# receiver.net
KiCad netlist of a schematic drawn in EAGLE
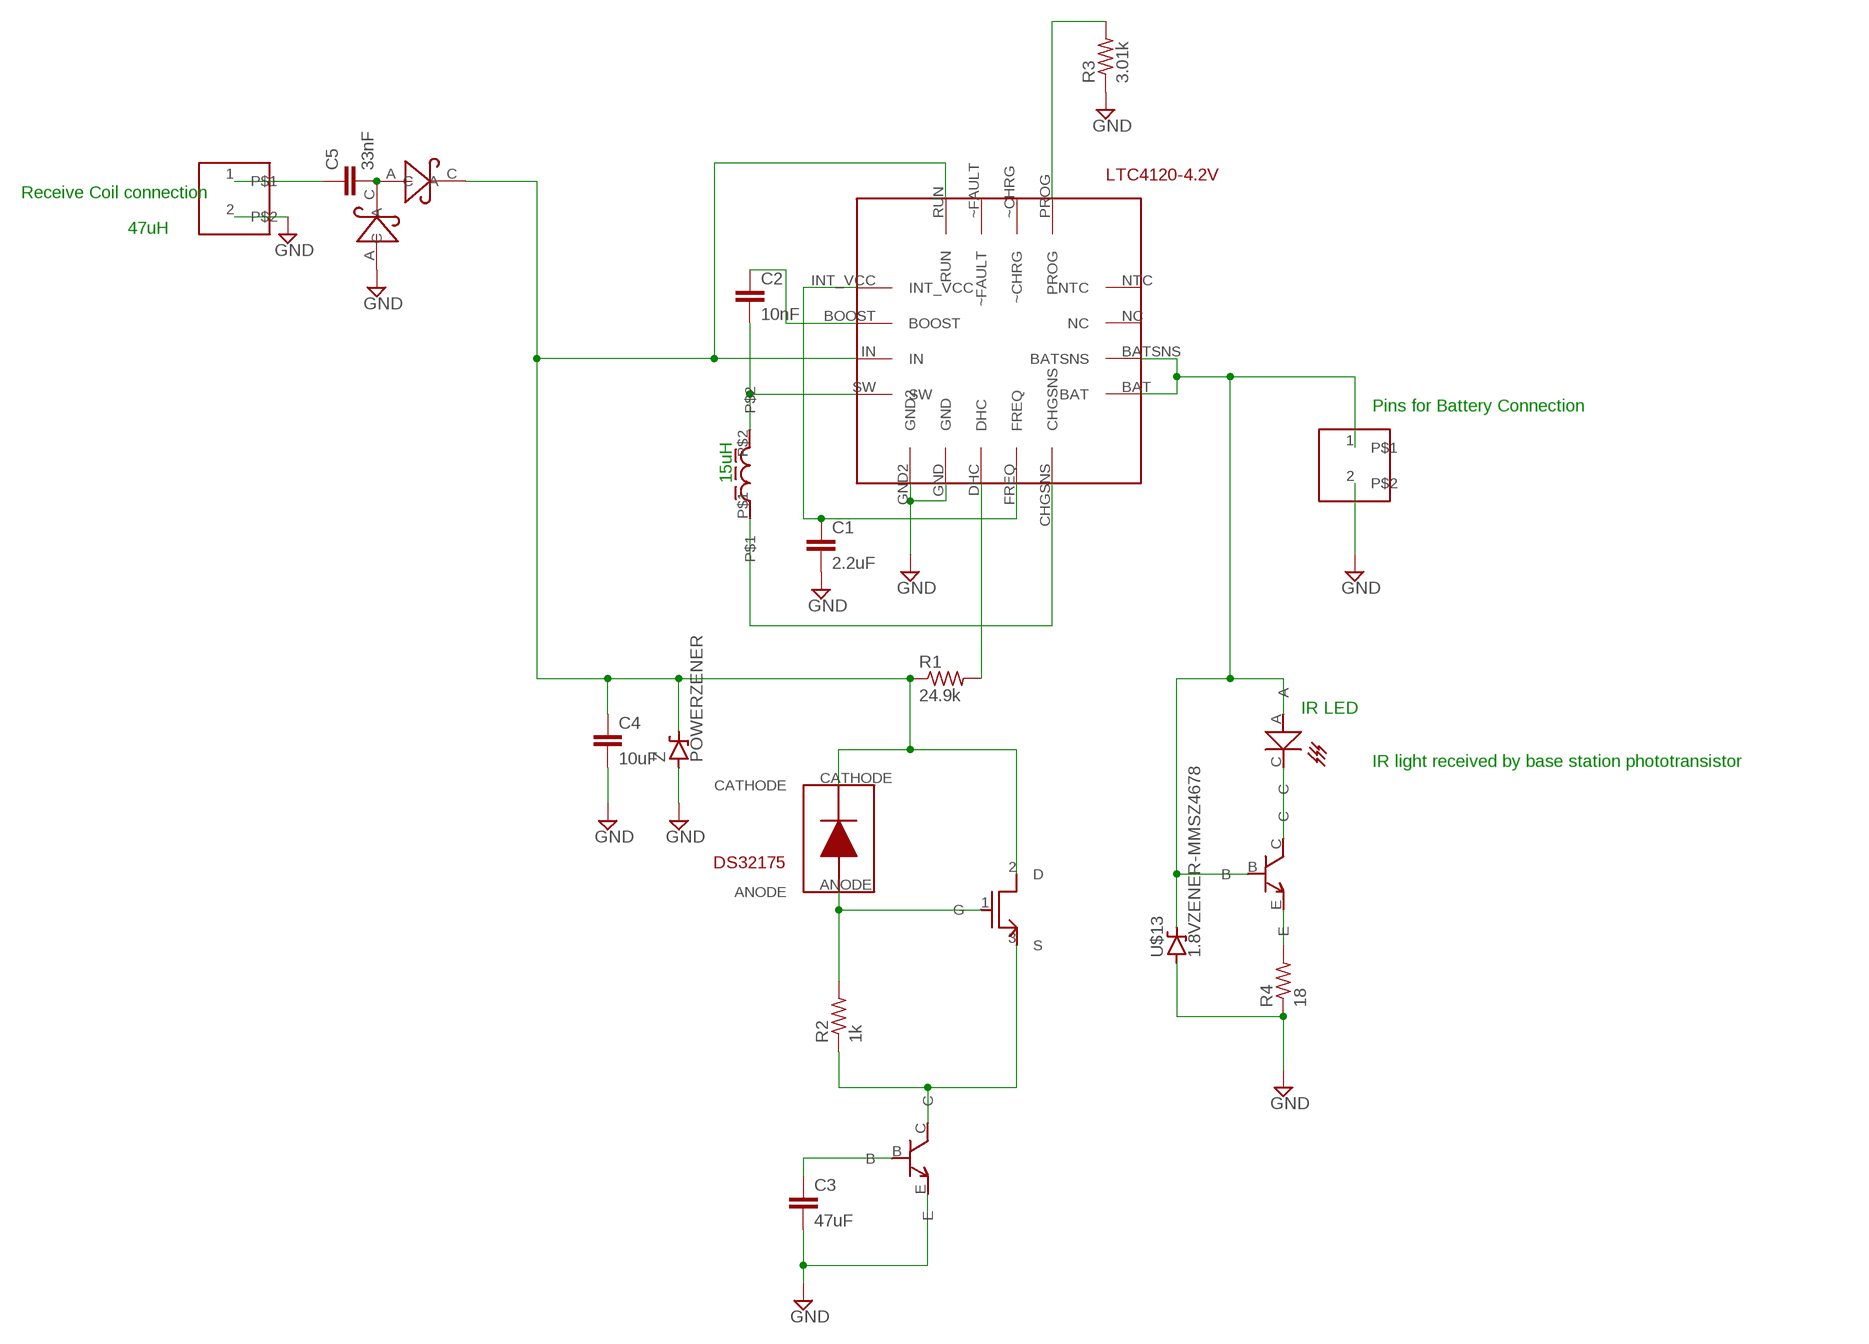
[diagram p0: schematic, sheet 1]

(export (version "E")
  (design (tool "Eeschema 10.0.6"))
  (components
    (comp (ref "C1")
      (value "2.2uF")
      (footprint "eagle-import:C0805K")
      (libsource (lib "eagle-import") (part "C-EUC0805K"))
    )
    (comp (ref "C2")
      (value "10nF")
      (footprint "eagle-import:C0805K")
      (libsource (lib "eagle-import") (part "C-EUC0805K"))
    )
    (comp (ref "C3")
      (value "47uF")
      (footprint "eagle-import:C0805K")
      (libsource (lib "eagle-import") (part "C-EUC0805K"))
    )
    (comp (ref "C4")
      (value "10uF")
      (footprint "eagle-import:C0805K")
      (libsource (lib "eagle-import") (part "C-EUC0805K"))
    )
    (comp (ref "C5")
      (value "33nF")
      (footprint "eagle-import:C0805K")
      (libsource (lib "eagle-import") (part "C-EUC0805K"))
    )
    (comp (ref "PS")
      (value "SCHTKYPOWER")
      (footprint "eagle-import:POWERDI123")
      (libsource (lib "eagle-import") (part "SCHTKYPOWER"))
    )
    (comp (ref "PS2")
      (value "SCHTKYPOWER")
      (footprint "eagle-import:POWERDI123")
      (libsource (lib "eagle-import") (part "SCHTKYPOWER"))
    )
    (comp (ref "R1")
      (value "24.9k")
      (footprint "eagle-import:R0805")
      (libsource (lib "eagle-import") (part "R-US_R0805"))
    )
    (comp (ref "R2")
      (value "1k")
      (footprint "eagle-import:R0805")
      (libsource (lib "eagle-import") (part "R-US_R0805"))
    )
    (comp (ref "R3")
      (value "3.01k")
      (footprint "eagle-import:R0805")
      (libsource (lib "eagle-import") (part "R-US_R0805"))
    )
    (comp (ref "R4")
      (value "18")
      (footprint "eagle-import:R0805")
      (libsource (lib "eagle-import") (part "R-US_R0805"))
    )
    (comp (ref "U$1")
      (value "LTC4120-4.2V")
      (footprint "eagle-import:LTC4120-4.2V")
      (libsource (lib "eagle-import") (part "LTC4120-4.2V"))
    )
    (comp (ref "U$2")
      (value "1X02")
      (footprint "eagle-import:1X02")
      (libsource (lib "eagle-import") (part "1X02"))
    )
    (comp (ref "U$3")
      (value "15UH-INDUCTOR")
      (footprint "eagle-import:15UH-INDUCTOR")
      (libsource (lib "eagle-import") (part "15UH-INDUCTOR"))
    )
    (comp (ref "U$4")
      (value "BAS521")
      (footprint "eagle-import:BAS521-V-DIODE")
      (libsource (lib "eagle-import") (part "BAS521"))
    )
    (comp (ref "U$5")
      (value "M1-RSD140P06")
      (footprint "eagle-import:DPAKTO252")
      (libsource (lib "eagle-import") (part "M1-RSD140P06"))
    )
    (comp (ref "U$6")
      (value "NPN-MMBT3904")
      (footprint "eagle-import:SOT23")
      (libsource (lib "eagle-import") (part "NPN-MMBT3904"))
    )
    (comp (ref "U$10")
      (value "1X02")
      (footprint "eagle-import:1X02")
      (libsource (lib "eagle-import") (part "1X02"))
    )
    (comp (ref "U$11")
      (value "IRLED")
      (footprint "eagle-import:IRLED")
      (libsource (lib "eagle-import") (part "IRLED"))
    )
    (comp (ref "U$13")
      (value "1.8VZENER-MMSZ4678")
      (footprint "eagle-import:SOD-123")
      (libsource (lib "eagle-import") (part "1.8VZENER-MMSZ4678"))
    )
    (comp (ref "U$14")
      (value "NPN-MMBT3904")
      (footprint "eagle-import:SOT23")
      (libsource (lib "eagle-import") (part "NPN-MMBT3904"))
    )
    (comp (ref "Z")
      (value "POWERZENER")
      (footprint "eagle-import:POWERDI123")
      (libsource (lib "eagle-import") (part "POWERZENER"))
    )
  )
  (nets
    (net (code "1") (name "GND") (class "Default")
      (node (ref "C1") (pin "2") (pinfunction "2_2") (pintype "passive"))
      (node (ref "C3") (pin "2") (pinfunction "2_2") (pintype "passive"))
      (node (ref "C4") (pin "2") (pinfunction "2_2") (pintype "passive"))
      (node (ref "PS2") (pin "A") (pinfunction "A_A") (pintype "bidirectional"))
      (node (ref "R3") (pin "1") (pinfunction "1_1") (pintype "passive"))
      (node (ref "R4") (pin "1") (pinfunction "1_1") (pintype "passive"))
      (node (ref "U$1") (pin "GND") (pinfunction "GND_GND") (pintype "bidirectional"))
      (node (ref "U$1") (pin "GND2") (pinfunction "GND2_GND2") (pintype "bidirectional"))
      (node (ref "U$10") (pin "2") (pinfunction "P$2_2") (pintype "bidirectional"))
      (node (ref "U$13") (pin "A") (pinfunction "A_A") (pintype "passive"))
      (node (ref "U$2") (pin "2") (pinfunction "P$2_2") (pintype "bidirectional"))
      (node (ref "U$6") (pin "E") (pinfunction "E_E") (pintype "bidirectional"))
      (node (ref "Z") (pin "A") (pinfunction "A_A") (pintype "passive"))
    )
    (net (code "2") (name "Net-(C1-Pad1)") (class "Default")
      (node (ref "C1") (pin "1") (pinfunction "1_1") (pintype "passive"))
      (node (ref "U$1") (pin "FREQ") (pinfunction "FREQ_FREQ") (pintype "bidirectional"))
      (node (ref "U$1") (pin "INT_VCC") (pinfunction "INT_VCC_INT_VCC") (pintype "bidirectional"))
    )
    (net (code "3") (name "Net-(C2-Pad1)") (class "Default")
      (node (ref "C2") (pin "1") (pinfunction "1_1") (pintype "passive"))
      (node (ref "U$1") (pin "BOOST") (pinfunction "BOOST_BOOST") (pintype "bidirectional"))
    )
    (net (code "4") (name "Net-(C2-Pad2)") (class "Default")
      (node (ref "C2") (pin "2") (pinfunction "2_2") (pintype "passive"))
      (node (ref "U$1") (pin "SW") (pinfunction "SW_SW") (pintype "bidirectional"))
      (node (ref "U$3") (pin "P$2") (pinfunction "P$2_P$2") (pintype "bidirectional"))
    )
    (net (code "5") (name "Net-(C3-Pad1)") (class "Default")
      (node (ref "C3") (pin "1") (pinfunction "1_1") (pintype "passive"))
      (node (ref "U$6") (pin "B") (pinfunction "B_B") (pintype "bidirectional"))
    )
    (net (code "6") (name "Net-(C5-Pad2)") (class "Default")
      (node (ref "C5") (pin "2") (pinfunction "2_2") (pintype "passive"))
      (node (ref "PS") (pin "A") (pinfunction "A_A") (pintype "bidirectional"))
      (node (ref "PS2") (pin "C") (pinfunction "C_C") (pintype "bidirectional"))
    )
    (net (code "7") (name "Net-(R1-Pad2)") (class "Default")
      (node (ref "R1") (pin "2") (pinfunction "2_2") (pintype "passive"))
      (node (ref "U$1") (pin "DHC") (pinfunction "DHC_DHC") (pintype "bidirectional"))
    )
    (net (code "8") (name "Net-(R3-Pad2)") (class "Default")
      (node (ref "R3") (pin "2") (pinfunction "2_2") (pintype "passive"))
      (node (ref "U$1") (pin "PROG") (pinfunction "PROG_PROG") (pintype "bidirectional"))
    )
    (net (code "9") (name "Net-(R4-Pad2)") (class "Default")
      (node (ref "R4") (pin "2") (pinfunction "2_2") (pintype "passive"))
      (node (ref "U$14") (pin "E") (pinfunction "E_E") (pintype "bidirectional"))
    )
    (net (code "10") (name "Net-(U$1-PadCHGSNS)") (class "Default")
      (node (ref "U$1") (pin "CHGSNS") (pinfunction "CHGSNS_CHGSNS") (pintype "bidirectional"))
      (node (ref "U$3") (pin "P$1") (pinfunction "P$1_P$1") (pintype "bidirectional"))
    )
    (net (code "11") (name "Net-(U$2-P$1)") (class "Default")
      (node (ref "C5") (pin "1") (pinfunction "1_1") (pintype "passive"))
      (node (ref "U$2") (pin "1") (pinfunction "P$1_1") (pintype "bidirectional"))
    )
    (net (code "12") (name "Net-(U$5-D)") (class "Default")
      (node (ref "C4") (pin "1") (pinfunction "1_1") (pintype "passive"))
      (node (ref "PS") (pin "C") (pinfunction "C_C") (pintype "bidirectional"))
      (node (ref "R1") (pin "1") (pinfunction "1_1") (pintype "passive"))
      (node (ref "U$1") (pin "IN") (pinfunction "IN_IN") (pintype "bidirectional"))
      (node (ref "U$1") (pin "RUN") (pinfunction "RUN_RUN") (pintype "bidirectional"))
      (node (ref "U$4") (pin "CATHODE") (pinfunction "CATHODE_CATHODE") (pintype "bidirectional"))
      (node (ref "U$5") (pin "2") (pinfunction "D_2") (pintype "bidirectional"))
      (node (ref "Z") (pin "C") (pinfunction "C_C") (pintype "passive"))
    )
    (net (code "13") (name "Net-(U$5-G)") (class "Default")
      (node (ref "R2") (pin "2") (pinfunction "2_2") (pintype "passive"))
      (node (ref "U$4") (pin "ANODE") (pinfunction "ANODE_ANODE") (pintype "bidirectional"))
      (node (ref "U$5") (pin "1") (pinfunction "G_1") (pintype "bidirectional"))
    )
    (net (code "14") (name "Net-(U$5-S)") (class "Default")
      (node (ref "R2") (pin "1") (pinfunction "1_1") (pintype "passive"))
      (node (ref "U$5") (pin "3") (pinfunction "S_3") (pintype "bidirectional"))
      (node (ref "U$6") (pin "C") (pinfunction "C_C") (pintype "bidirectional"))
    )
    (net (code "15") (name "Net-(U$10-P$1)") (class "Default")
      (node (ref "U$1") (pin "BAT") (pinfunction "BAT_BAT") (pintype "bidirectional"))
      (node (ref "U$1") (pin "BATSNS") (pinfunction "BATSNS_BATSNS") (pintype "bidirectional"))
      (node (ref "U$10") (pin "1") (pinfunction "P$1_1") (pintype "bidirectional"))
      (node (ref "U$11") (pin "A") (pinfunction "A_A") (pintype "bidirectional"))
      (node (ref "U$13") (pin "C") (pinfunction "C_C") (pintype "passive"))
      (node (ref "U$14") (pin "B") (pinfunction "B_B") (pintype "bidirectional"))
    )
    (net (code "16") (name "Net-(U$11-PadC)") (class "Default")
      (node (ref "U$11") (pin "C") (pinfunction "C_C") (pintype "bidirectional"))
      (node (ref "U$14") (pin "C") (pinfunction "C_C") (pintype "bidirectional"))
    )
    (net (code "17") (name "unconnected-(U$1-PadNC)") (class "Default")
      (node (ref "U$1") (pin "NC") (pinfunction "NC_NC") (pintype "bidirectional"))
    )
    (net (code "18") (name "unconnected-(U$1-PadNTC)") (class "Default")
      (node (ref "U$1") (pin "NTC") (pinfunction "NTC_NTC") (pintype "bidirectional"))
    )
    (net (code "19") (name "unconnected-(U$1-~{CHRG}-Pad~CHRG)") (class "Default")
      (node (ref "U$1") (pin "~CHRG") (pinfunction "~{CHRG}_~CHRG") (pintype "bidirectional"))
    )
    (net (code "20") (name "unconnected-(U$1-~{FAULT}-Pad~FAULT)") (class "Default")
      (node (ref "U$1") (pin "~FAULT") (pinfunction "~{FAULT}_~FAULT") (pintype "bidirectional"))
    )
  )
)
